# PAGE05_FPGA_Config.net
KiCad netlist of a schematic drawn in Altium Designer
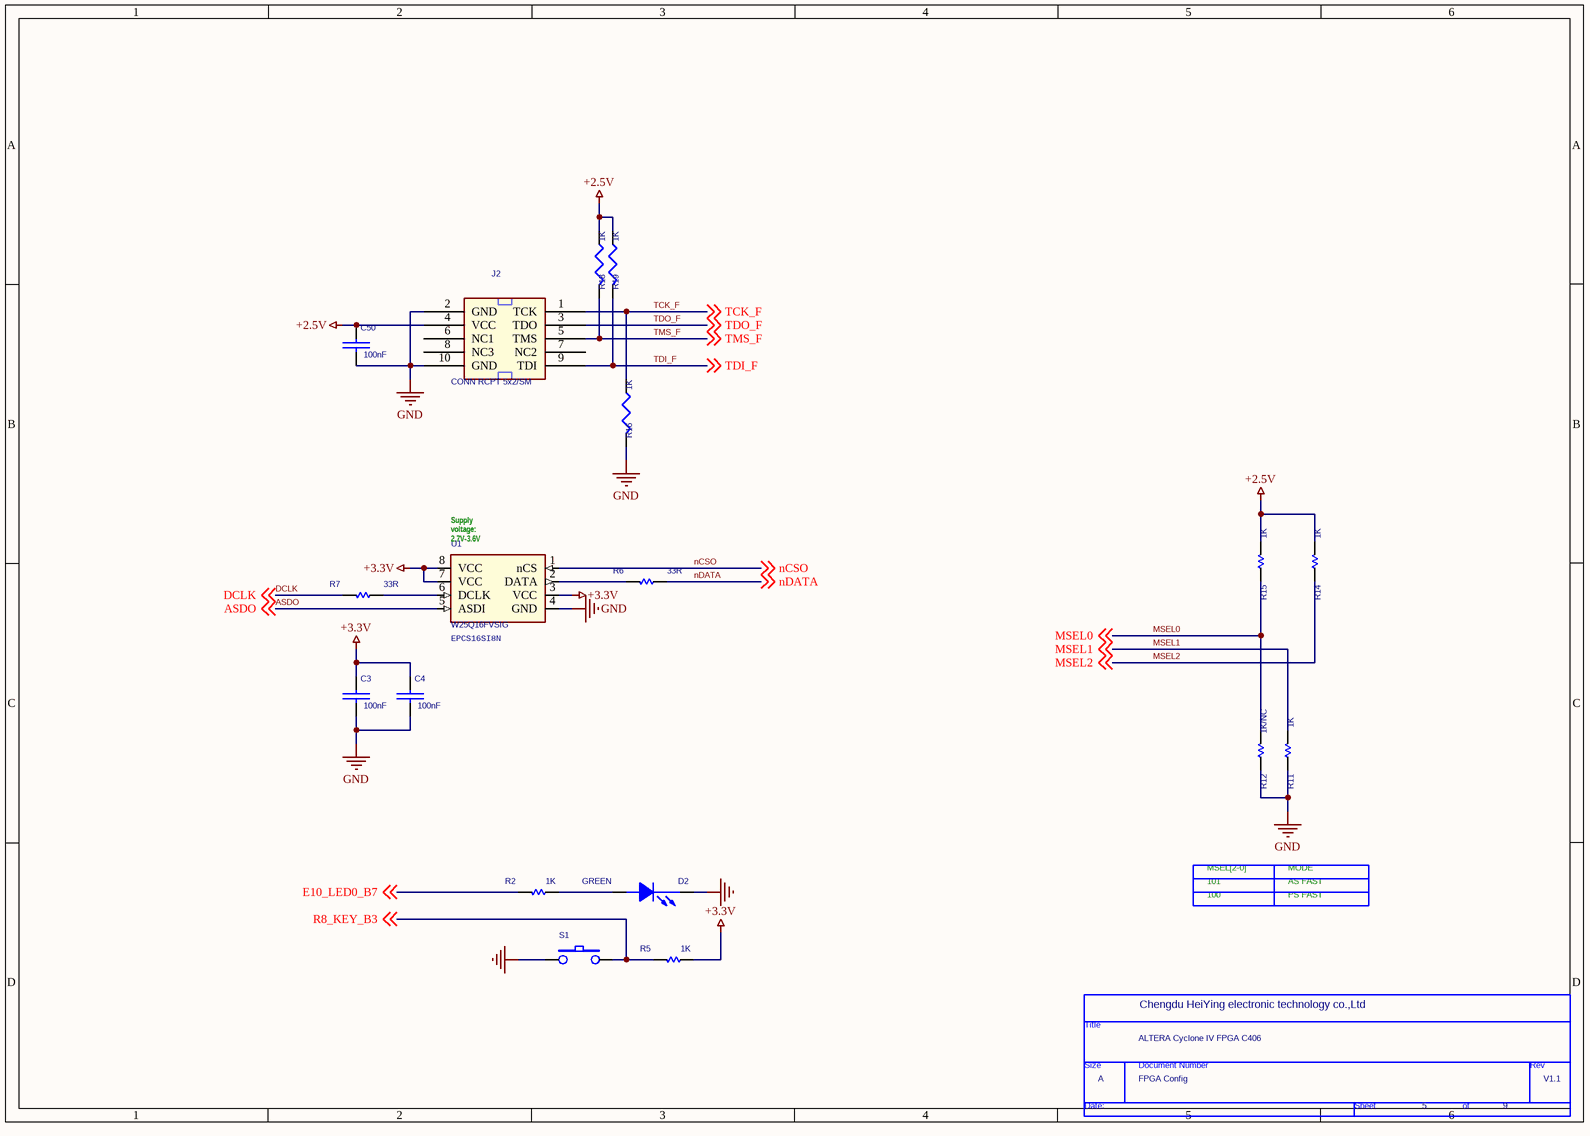
[diagram p0: PAGE05 FPGA Config.SchDoc]

(export (version "E")
  (design (tool "Eeschema 10.0.6"))
  (components
    (comp (ref "C3")
      (value "100nF")
      (description "CAP CER .1UF 16V X7R 0402")
      (fields (field (name "MANUFACTURER") "MURATA"))
      (libsource (lib "*") (part "CAP_0"))
    )
    (comp (ref "C4")
      (value "100nF")
      (description "CAP CER .1UF 16V X7R 0402")
      (fields (field (name "MANUFACTURER") "MURATA"))
      (libsource (lib "*") (part "CAP_0"))
    )
    (comp (ref "C50")
      (value "100nF")
      (description "CAP CER .1UF 16V X7R 0402")
      (fields (field (name "MANUFACTURER") "MURATA"))
      (libsource (lib "*") (part "CAP_0"))
    )
    (comp (ref "D2") (value "GREEN") (libsource (lib "*") (part "LED")))
    (comp (ref "J2") (value "CONN RCPT 5x2/SM") (libsource (lib "*") (part "CONN RCPT 5x2/SM_0")))
    (comp (ref "R2") (value "1K") (libsource (lib "*") (part "SMALL R1")))
    (comp (ref "R5") (value "1K") (libsource (lib "*") (part "SMALL R1")))
    (comp (ref "R6") (value "33R") (libsource (lib "*") (part "SMALL R1")))
    (comp (ref "R7") (value "33R") (libsource (lib "*") (part "SMALL R1")))
    (comp (ref "R11") (value "1K") (libsource (lib "*") (part "SMALL R1")))
    (comp (ref "R12") (value "1K/NC") (libsource (lib "*") (part "SMALL R1")))
    (comp (ref "R14") (value "1K") (libsource (lib "*") (part "SMALL R1")))
    (comp (ref "R15") (value "1K") (libsource (lib "*") (part "SMALL R1")))
    (comp (ref "R16") (value "1K") (libsource (lib "*") (part "R_6")))
    (comp (ref "R18") (value "1K") (libsource (lib "*") (part "R_6")))
    (comp (ref "R19") (value "1K") (libsource (lib "*") (part "R_6")))
    (comp (ref "S1")
      (value "FSMRA2JH")
      (description "SWITCH TACT RA H=3.86MM 160GF")
      (fields (field (name "MANUFACTURER") "TYCO"))
      (libsource (lib "*") (part "SWITCH_2"))
    )
    (comp (ref "U1") (value "W25Q16FVSIG") (libsource (lib "*") (part "EPCS1SI8N_0")))
  )
  (nets
    (net (code "1") (name "+2.5V") (class "Default")
      (node (ref "C50") (pin "1") (pinfunction "1_1") (pintype "passive"))
      (node (ref "J2") (pin "4") (pinfunction "VCC_4") (pintype "power_in"))
      (node (ref "R14") (pin "2") (pinfunction "2_2") (pintype "passive"))
      (node (ref "R15") (pin "2") (pinfunction "2_2") (pintype "passive"))
      (node (ref "R18") (pin "1") (pinfunction "1_1") (pintype "passive"))
      (node (ref "R19") (pin "1") (pinfunction "1_1") (pintype "passive"))
    )
    (net (code "2") (name "+3.3V") (class "Default")
      (node (ref "C3") (pin "1") (pinfunction "1_1") (pintype "passive"))
      (node (ref "C4") (pin "1") (pinfunction "1_1") (pintype "passive"))
      (node (ref "R5") (pin "1") (pinfunction "1_1") (pintype "passive"))
      (node (ref "U1") (pin "3") (pinfunction "VCC_3") (pintype "power_in"))
      (node (ref "U1") (pin "7") (pinfunction "VCC_7") (pintype "power_in"))
      (node (ref "U1") (pin "8") (pinfunction "VCC_8") (pintype "power_in"))
    )
    (net (code "3") (name "ASDO") (class "Default")
      (node (ref "U1") (pin "5") (pinfunction "ASDI_5") (pintype "input"))
    )
    (net (code "4") (name "DCLK") (class "Default")
      (node (ref "R7") (pin "2") (pinfunction "2_2") (pintype "passive"))
    )
    (net (code "5") (name "E10_LED0_B7") (class "Default")
      (node (ref "R2") (pin "2") (pinfunction "2_2") (pintype "passive"))
    )
    (net (code "6") (name "GND") (class "Default")
      (node (ref "C3") (pin "2") (pinfunction "2_2") (pintype "passive"))
      (node (ref "C4") (pin "2") (pinfunction "2_2") (pintype "passive"))
      (node (ref "C50") (pin "2") (pinfunction "2_2") (pintype "passive"))
      (node (ref "D2") (pin "2") (pinfunction "CATHODE_2") (pintype "passive"))
      (node (ref "J2") (pin "10") (pinfunction "GND_10") (pintype "power_in"))
      (node (ref "J2") (pin "2") (pinfunction "GND_2") (pintype "power_in"))
      (node (ref "R11") (pin "1") (pinfunction "1_1") (pintype "passive"))
      (node (ref "R12") (pin "1") (pinfunction "1_1") (pintype "passive"))
      (node (ref "R16") (pin "2") (pinfunction "2_2") (pintype "passive"))
      (node (ref "S1") (pin "2") (pinfunction "2_2") (pintype "passive"))
      (node (ref "U1") (pin "4") (pinfunction "GND_4") (pintype "power_in"))
    )
    (net (code "7") (name "MSEL0") (class "Default")
      (node (ref "R12") (pin "2") (pinfunction "2_2") (pintype "passive"))
      (node (ref "R15") (pin "1") (pinfunction "1_1") (pintype "passive"))
    )
    (net (code "8") (name "MSEL1") (class "Default")
      (node (ref "R11") (pin "2") (pinfunction "2_2") (pintype "passive"))
    )
    (net (code "9") (name "MSEL2") (class "Default")
      (node (ref "R14") (pin "1") (pinfunction "1_1") (pintype "passive"))
    )
    (net (code "10") (name "Net-(D2-ANODE)") (class "Default")
      (node (ref "D2") (pin "1") (pinfunction "ANODE_1") (pintype "passive"))
      (node (ref "R2") (pin "1") (pinfunction "1_1") (pintype "passive"))
    )
    (net (code "11") (name "Net-(U1-DATA)") (class "Default")
      (node (ref "R6") (pin "2") (pinfunction "2_2") (pintype "passive"))
      (node (ref "U1") (pin "2") (pinfunction "DATA_2") (pintype "output"))
    )
    (net (code "12") (name "Net-(U1-DCLK)") (class "Default")
      (node (ref "R7") (pin "1") (pinfunction "1_1") (pintype "passive"))
      (node (ref "U1") (pin "6") (pinfunction "DCLK_6") (pintype "input"))
    )
    (net (code "13") (name "R8_KEY_B3") (class "Default")
      (node (ref "R5") (pin "2") (pinfunction "2_2") (pintype "passive"))
      (node (ref "S1") (pin "1") (pinfunction "1_1") (pintype "passive"))
    )
    (net (code "14") (name "TCK_F") (class "Default")
      (node (ref "J2") (pin "1") (pinfunction "TCK_1") (pintype "passive"))
      (node (ref "R16") (pin "1") (pinfunction "1_1") (pintype "passive"))
    )
    (net (code "15") (name "TDI_F") (class "Default")
      (node (ref "J2") (pin "9") (pinfunction "TDI_9") (pintype "passive"))
      (node (ref "R19") (pin "2") (pinfunction "2_2") (pintype "passive"))
    )
    (net (code "16") (name "TDO_F") (class "Default")
      (node (ref "J2") (pin "3") (pinfunction "TDO_3") (pintype "passive"))
    )
    (net (code "17") (name "TMS_F") (class "Default")
      (node (ref "J2") (pin "5") (pinfunction "TMS_5") (pintype "passive"))
      (node (ref "R18") (pin "2") (pinfunction "2_2") (pintype "passive"))
    )
    (net (code "18") (name "nCSO") (class "Default")
      (node (ref "U1") (pin "1") (pinfunction "nCS_1") (pintype "input"))
    )
    (net (code "19") (name "nDATA") (class "Default")
      (node (ref "R6") (pin "1") (pinfunction "1_1") (pintype "passive"))
    )
    (net (code "20") (name "unconnected-(J2-NC1-Pad6)") (class "Default")
      (node (ref "J2") (pin "6") (pinfunction "NC1_6") (pintype "passive"))
    )
    (net (code "21") (name "unconnected-(J2-NC2-Pad7)") (class "Default")
      (node (ref "J2") (pin "7") (pinfunction "NC2_7") (pintype "passive"))
    )
    (net (code "22") (name "unconnected-(J2-NC3-Pad8)") (class "Default")
      (node (ref "J2") (pin "8") (pinfunction "NC3_8") (pintype "passive"))
    )
  )
)
